# CATS-Vega-IMU.net
KiCad netlist of a schematic drawn in Altium Designer
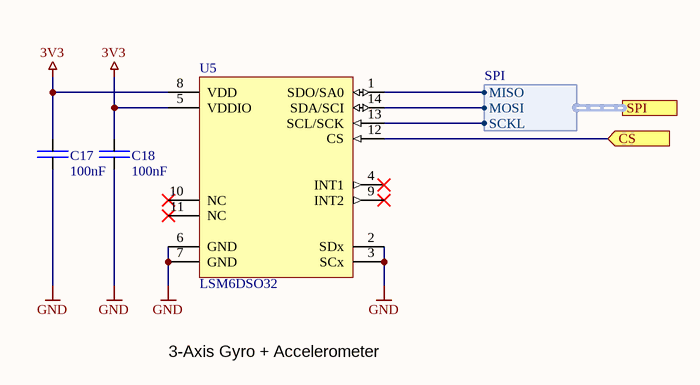
[diagram p0: CATS-Vega-IMU.SchDoc]

(export (version "E")
  (design (tool "Eeschema 10.0.6"))
  (components
    (comp (ref "C17")
      (value "100nF")
      (footprint "SMD Keramikkondensator 0603")
      (description "SMD Ceramic Capacitor E6")
      (libsource (lib "CATS-EUROC") (part "E6 - 100nF"))
    )
    (comp (ref "C18")
      (value "100nF")
      (footprint "SMD Keramikkondensator 0603")
      (description "SMD Ceramic Capacitor E6")
      (libsource (lib "CATS-EUROC") (part "E6 - 100nF"))
    )
    (comp (ref "U5")
      (value "LSM6DSO32")
      (footprint "SMD IC LGA-14")
      (description "iNEMO inertial module\r\n±4/±8/±16/±32 g \r\n±125/±250/±500/±1000/±2000 dps")
      (libsource (lib "Sensors") (part "LSM6DSO32"))
    )
  )
  (nets
    (net (code "2") (name "/CS") (class "Default")
      (node (ref "U5") (pin "12") (pinfunction "CS_12") (pintype "input"))
    )
    (net (code "3") (name "/MISO") (class "Default")
      (node (ref "U5") (pin "1") (pinfunction "SDO/SA0_1") (pintype "bidirectional"))
    )
    (net (code "4") (name "/MOSI") (class "Default")
      (node (ref "U5") (pin "14") (pinfunction "SDA/SCI_14") (pintype "bidirectional"))
    )
    (net (code "5") (name "/SCKL") (class "Default")
      (node (ref "U5") (pin "13") (pinfunction "SCL/SCK_13") (pintype "input"))
    )
    (net (code "7") (name "3V3") (class "Default")
      (node (ref "C17") (pin "2") (pinfunction "2_2") (pintype "passive"))
      (node (ref "C18") (pin "2") (pinfunction "2_2") (pintype "passive"))
      (node (ref "U5") (pin "5") (pinfunction "VDDIO_5") (pintype "passive"))
      (node (ref "U5") (pin "8") (pinfunction "VDD_8") (pintype "passive"))
    )
    (net (code "8") (name "GND") (class "Default")
      (node (ref "C17") (pin "1") (pinfunction "1_1") (pintype "passive"))
      (node (ref "C18") (pin "1") (pinfunction "1_1") (pintype "passive"))
      (node (ref "U5") (pin "2") (pinfunction "SDx_2") (pintype "passive"))
      (node (ref "U5") (pin "3") (pinfunction "SCx_3") (pintype "passive"))
      (node (ref "U5") (pin "6") (pinfunction "GND_6") (pintype "passive"))
      (node (ref "U5") (pin "7") (pinfunction "GND_7") (pintype "passive"))
    )
    (net (code "9") (name "unconnected-(U5-INT1-Pad4)") (class "Default")
      (node (ref "U5") (pin "4") (pinfunction "INT1_4") (pintype "output+no_connect"))
    )
    (net (code "10") (name "unconnected-(U5-INT2-Pad9)") (class "Default")
      (node (ref "U5") (pin "9") (pinfunction "INT2_9") (pintype "output+no_connect"))
    )
    (net (code "11") (name "unconnected-(U5-NC-Pad10)") (class "Default")
      (node (ref "U5") (pin "10") (pinfunction "NC_10") (pintype "passive+no_connect"))
    )
    (net (code "12") (name "unconnected-(U5-NC-Pad11)") (class "Default")
      (node (ref "U5") (pin "11") (pinfunction "NC_11") (pintype "passive+no_connect"))
    )
  )
)
